# ESC.net
KiCad netlist of a schematic drawn in Altium Designer
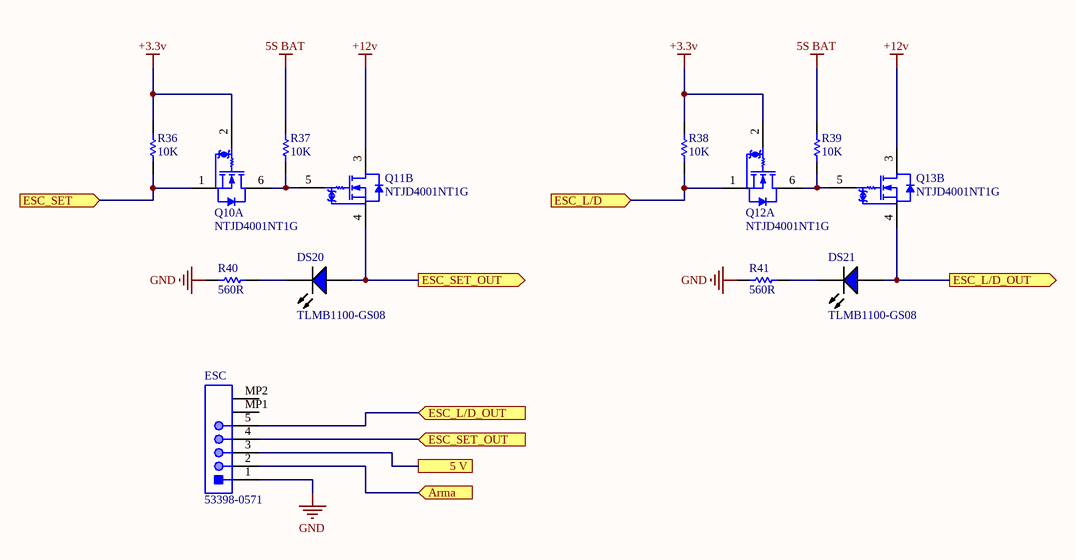
[diagram p0: ESC.SchDoc]

(export (version "E")
  (design (tool "Eeschema 10.0.6"))
  (components
    (comp (ref "DS20")
      (value "TLMB1100-GS08")
      (footprint "VISH-TLMX1100-2_V")
      (fields (field (name "TOLERANCE") "10%"))
      (libsource (lib "Altium Content Vault") (part "CMP-1666-00028-1"))
    )
    (comp (ref "DS21")
      (value "TLMB1100-GS08")
      (footprint "VISH-TLMX1100-2_V")
      (fields (field (name "TOLERANCE") "10%"))
      (libsource (lib "Altium Content Vault") (part "CMP-1666-00028-1"))
    )
    (comp (ref "ESC")
      (value "53398-0571")
      (footprint "MOLX-53398-0571-5_V")
      (fields (field (name "MANUFACTURER") "Molex"))
      (libsource (lib "Moles_53398-0571") (part "CMP-2000-05250-1"))
    )
    (comp (ref "Q10")
      (value "NTJD4001NT1G")
      (footprint "ONSC-SOT-363-6-419B-02_W_V")
      (fields (field (name "MANUFACTURER") "On Semiconductor"))
      (libsource (lib "Altium Content Vault") (part "ONSC-NNMOS-6_D"))
    )
    (comp (ref "Q11")
      (value "NTJD4001NT1G")
      (footprint "ONSC-SOT-363-6-419B-02_W_V")
      (fields (field (name "MANUFACTURER") "On Semiconductor"))
      (libsource (lib "Altium Content Vault") (part "ONSC-NNMOS-6_D"))
    )
    (comp (ref "Q12")
      (value "NTJD4001NT1G")
      (footprint "ONSC-SOT-363-6-419B-02_W_V")
      (fields (field (name "MANUFACTURER") "On Semiconductor"))
      (libsource (lib "Altium Content Vault") (part "ONSC-NNMOS-6_D"))
    )
    (comp (ref "Q13")
      (value "NTJD4001NT1G")
      (footprint "ONSC-SOT-363-6-419B-02_W_V")
      (fields (field (name "MANUFACTURER") "On Semiconductor"))
      (libsource (lib "Altium Content Vault") (part "ONSC-NNMOS-6_D"))
    )
    (comp (ref "R36")
      (value "10K")
      (footprint "RES-0402")
      (fields (field (name "Comment") "CRCW040210K0FKEDC"))
      (libsource (lib "Schlib1") (part "RES 1K 0402"))
    )
    (comp (ref "R37")
      (value "10K")
      (footprint "RES-0402")
      (fields (field (name "Comment") "CRCW040210K0FKEDC"))
      (libsource (lib "Schlib1") (part "RES 1K 0402"))
    )
    (comp (ref "R38")
      (value "10K")
      (footprint "RES-0402")
      (fields (field (name "Comment") "CRCW040210K0FKEDC"))
      (libsource (lib "Schlib1") (part "RES 1K 0402"))
    )
    (comp (ref "R39")
      (value "10K")
      (footprint "RES-0402")
      (fields (field (name "Comment") "CRCW040210K0FKEDC"))
      (libsource (lib "Schlib1") (part "RES 1K 0402"))
    )
    (comp (ref "R40")
      (value "560R")
      (footprint "RES-0402")
      (fields (field (name "Comment") "RR0510P-561-D"))
      (libsource (lib "Schlib1") (part "RES 1K 0402"))
    )
    (comp (ref "R41")
      (value "560R")
      (footprint "RES-0402")
      (fields (field (name "Comment") "RR0510P-561-D"))
      (libsource (lib "Schlib1") (part "RES 1K 0402"))
    )
  )
  (nets
    (net (code "1") (name "+3.3v") (class "Default")
      (node (ref "Q10") (pin "2") (pinfunction "G1_2") (pintype "passive"))
      (node (ref "Q12") (pin "2") (pinfunction "G1_2") (pintype "passive"))
      (node (ref "R36") (pin "2") (pinfunction "2_2") (pintype "passive"))
      (node (ref "R38") (pin "2") (pinfunction "2_2") (pintype "passive"))
    )
    (net (code "2") (name "+12v") (class "Default")
      (node (ref "Q11") (pin "3") (pinfunction "D2_3") (pintype "passive"))
      (node (ref "Q13") (pin "3") (pinfunction "D2_3") (pintype "passive"))
    )
    (net (code "3") (name "/5 V") (class "Default")
      (node (ref "ESC") (pin "3") (pinfunction "3_3") (pintype "passive"))
    )
    (net (code "4") (name "/Arma") (class "Default")
      (node (ref "ESC") (pin "2") (pinfunction "2_2") (pintype "passive"))
    )
    (net (code "5") (name "/ESC_L{slash}D") (class "Default")
      (node (ref "Q12") (pin "1") (pinfunction "S1_1") (pintype "passive"))
      (node (ref "R38") (pin "1") (pinfunction "1_1") (pintype "passive"))
    )
    (net (code "6") (name "/ESC_L{slash}D_OUT") (class "Default")
      (node (ref "DS21") (pin "1") (pinfunction "A_1") (pintype "passive"))
      (node (ref "ESC") (pin "5") (pinfunction "5_5") (pintype "passive"))
      (node (ref "Q13") (pin "4") (pinfunction "S2_4") (pintype "passive"))
    )
    (net (code "7") (name "/ESC_SET") (class "Default")
      (node (ref "Q10") (pin "1") (pinfunction "S1_1") (pintype "passive"))
      (node (ref "R36") (pin "1") (pinfunction "1_1") (pintype "passive"))
    )
    (net (code "8") (name "/ESC_SET_OUT") (class "Default")
      (node (ref "DS20") (pin "1") (pinfunction "A_1") (pintype "passive"))
      (node (ref "ESC") (pin "4") (pinfunction "4_4") (pintype "passive"))
      (node (ref "Q11") (pin "4") (pinfunction "S2_4") (pintype "passive"))
    )
    (net (code "9") (name "5S BAT") (class "Default")
      (node (ref "R37") (pin "2") (pinfunction "2_2") (pintype "passive"))
      (node (ref "R39") (pin "2") (pinfunction "2_2") (pintype "passive"))
    )
    (net (code "10") (name "GND") (class "Default")
      (node (ref "ESC") (pin "1") (pinfunction "1_1") (pintype "passive"))
      (node (ref "R40") (pin "1") (pinfunction "1_1") (pintype "passive"))
      (node (ref "R41") (pin "1") (pinfunction "1_1") (pintype "passive"))
    )
    (net (code "11") (name "Net-(DS20-K)") (class "Default")
      (node (ref "DS20") (pin "2") (pinfunction "K_2") (pintype "passive"))
      (node (ref "R40") (pin "2") (pinfunction "2_2") (pintype "passive"))
    )
    (net (code "12") (name "Net-(DS21-K)") (class "Default")
      (node (ref "DS21") (pin "2") (pinfunction "K_2") (pintype "passive"))
      (node (ref "R41") (pin "2") (pinfunction "2_2") (pintype "passive"))
    )
    (net (code "13") (name "Net-(Q10A-D1)") (class "Default")
      (node (ref "Q10") (pin "6") (pinfunction "D1_6") (pintype "passive"))
      (node (ref "Q11") (pin "5") (pinfunction "G2_5") (pintype "passive"))
      (node (ref "R37") (pin "1") (pinfunction "1_1") (pintype "passive"))
    )
    (net (code "14") (name "Net-(Q12A-D1)") (class "Default")
      (node (ref "Q12") (pin "6") (pinfunction "D1_6") (pintype "passive"))
      (node (ref "Q13") (pin "5") (pinfunction "G2_5") (pintype "passive"))
      (node (ref "R39") (pin "1") (pinfunction "1_1") (pintype "passive"))
    )
    (net (code "15") (name "unconnected-(ESC-PadMP1)") (class "Default")
      (node (ref "ESC") (pin "MP1") (pinfunction "MP1_MP1") (pintype "passive"))
    )
    (net (code "16") (name "unconnected-(ESC-PadMP2)") (class "Default")
      (node (ref "ESC") (pin "MP2") (pinfunction "MP2_MP2") (pintype "passive"))
    )
  )
)
